# umodular_fader8.net
KiCad netlist of a schematic drawn in EAGLE
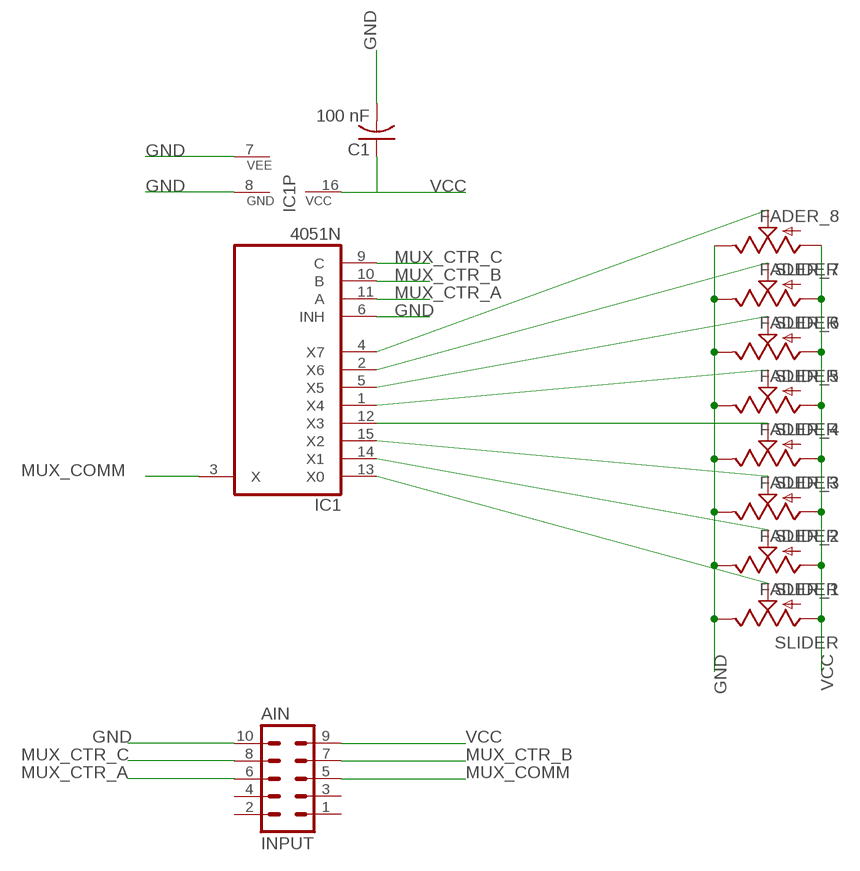
[diagram p0: schematic, sheet 1]

(export (version "E")
  (design (tool "Eeschema 10.0.6"))
  (components
    (comp (ref "AIN")
      (value "INPUT")
      (footprint "eagle-import:MA05-2")
      (libsource (lib "eagle-import") (part "MA05-2"))
    )
    (comp (ref "C1")
      (value "100 nF")
      (footprint "eagle-import:C050-024X044")
      (libsource (lib "eagle-import") (part "C-US050-024X044"))
    )
    (comp (ref "FADER_1")
      (value "SLIDER")
      (footprint "eagle-import:SLIDER")
      (libsource (lib "eagle-import") (part "SLIDER"))
    )
    (comp (ref "FADER_2")
      (value "SLIDER")
      (footprint "eagle-import:SLIDER")
      (libsource (lib "eagle-import") (part "SLIDER"))
    )
    (comp (ref "FADER_3")
      (value "SLIDER")
      (footprint "eagle-import:SLIDER")
      (libsource (lib "eagle-import") (part "SLIDER"))
    )
    (comp (ref "FADER_4")
      (value "SLIDER")
      (footprint "eagle-import:SLIDER")
      (libsource (lib "eagle-import") (part "SLIDER"))
    )
    (comp (ref "FADER_5")
      (value "SLIDER")
      (footprint "eagle-import:SLIDER")
      (libsource (lib "eagle-import") (part "SLIDER"))
    )
    (comp (ref "FADER_6")
      (value "SLIDER")
      (footprint "eagle-import:SLIDER")
      (libsource (lib "eagle-import") (part "SLIDER"))
    )
    (comp (ref "FADER_7")
      (value "SLIDER")
      (footprint "eagle-import:SLIDER")
      (libsource (lib "eagle-import") (part "SLIDER"))
    )
    (comp (ref "FADER_8")
      (value "SLIDER")
      (footprint "eagle-import:SLIDER")
      (libsource (lib "eagle-import") (part "SLIDER"))
    )
    (comp (ref "IC1")
      (value "4051N")
      (footprint "eagle-import:DIL16")
      (libsource (lib "eagle-import") (part "4051N"))
    )
  )
  (nets
    (net (code "1") (name "/GND") (class "Default")
      (node (ref "AIN") (pin "10") (pinfunction "10_10") (pintype "passive"))
      (node (ref "C1") (pin "2") (pinfunction "2_2") (pintype "passive"))
      (node (ref "FADER_1") (pin "1") (pinfunction "E_1") (pintype "passive"))
      (node (ref "FADER_2") (pin "1") (pinfunction "E_1") (pintype "passive"))
      (node (ref "FADER_3") (pin "1") (pinfunction "E_1") (pintype "passive"))
      (node (ref "FADER_4") (pin "1") (pinfunction "E_1") (pintype "passive"))
      (node (ref "FADER_5") (pin "1") (pinfunction "E_1") (pintype "passive"))
      (node (ref "FADER_6") (pin "1") (pinfunction "E_1") (pintype "passive"))
      (node (ref "FADER_7") (pin "1") (pinfunction "E_1") (pintype "passive"))
      (node (ref "FADER_8") (pin "1") (pinfunction "E_1") (pintype "passive"))
      (node (ref "IC1") (pin "6") (pinfunction "INH_6") (pintype "input"))
      (node (ref "IC1") (pin "7") (pinfunction "VEE_7") (pintype "power_in"))
      (node (ref "IC1") (pin "8") (pinfunction "GND_8") (pintype "power_in"))
    )
    (net (code "2") (name "/MUX_COMM") (class "Default")
      (node (ref "AIN") (pin "5") (pinfunction "5_5") (pintype "passive"))
      (node (ref "IC1") (pin "3") (pinfunction "X_3") (pintype "bidirectional"))
    )
    (net (code "3") (name "/MUX_CTR_A") (class "Default")
      (node (ref "AIN") (pin "6") (pinfunction "6_6") (pintype "passive"))
      (node (ref "IC1") (pin "11") (pinfunction "A_11") (pintype "input"))
    )
    (net (code "4") (name "/MUX_CTR_B") (class "Default")
      (node (ref "AIN") (pin "7") (pinfunction "7_7") (pintype "passive"))
      (node (ref "IC1") (pin "10") (pinfunction "B_10") (pintype "input"))
    )
    (net (code "5") (name "/MUX_CTR_C") (class "Default")
      (node (ref "AIN") (pin "8") (pinfunction "8_8") (pintype "passive"))
      (node (ref "IC1") (pin "9") (pinfunction "C_9") (pintype "input"))
    )
    (net (code "6") (name "/VCC") (class "Default")
      (node (ref "AIN") (pin "9") (pinfunction "9_9") (pintype "passive"))
      (node (ref "C1") (pin "1") (pinfunction "1_1") (pintype "passive"))
      (node (ref "FADER_1") (pin "3") (pinfunction "A_3") (pintype "passive"))
      (node (ref "FADER_2") (pin "3") (pinfunction "A_3") (pintype "passive"))
      (node (ref "FADER_3") (pin "3") (pinfunction "A_3") (pintype "passive"))
      (node (ref "FADER_4") (pin "3") (pinfunction "A_3") (pintype "passive"))
      (node (ref "FADER_5") (pin "3") (pinfunction "A_3") (pintype "passive"))
      (node (ref "FADER_6") (pin "3") (pinfunction "A_3") (pintype "passive"))
      (node (ref "FADER_7") (pin "3") (pinfunction "A_3") (pintype "passive"))
      (node (ref "FADER_8") (pin "3") (pinfunction "A_3") (pintype "passive"))
      (node (ref "IC1") (pin "16") (pinfunction "VCC_16") (pintype "power_in"))
    )
    (net (code "7") (name "Net-(FADER_1-S)") (class "Default")
      (node (ref "FADER_1") (pin "2A") (pinfunction "S_2A") (pintype "passive"))
      (node (ref "IC1") (pin "13") (pinfunction "X0_13") (pintype "bidirectional"))
    )
    (net (code "8") (name "Net-(FADER_2-S)") (class "Default")
      (node (ref "FADER_2") (pin "2A") (pinfunction "S_2A") (pintype "passive"))
      (node (ref "IC1") (pin "14") (pinfunction "X1_14") (pintype "bidirectional"))
    )
    (net (code "9") (name "Net-(FADER_3-S)") (class "Default")
      (node (ref "FADER_3") (pin "2A") (pinfunction "S_2A") (pintype "passive"))
      (node (ref "IC1") (pin "15") (pinfunction "X2_15") (pintype "bidirectional"))
    )
    (net (code "10") (name "Net-(FADER_4-S)") (class "Default")
      (node (ref "FADER_4") (pin "2A") (pinfunction "S_2A") (pintype "passive"))
      (node (ref "IC1") (pin "12") (pinfunction "X3_12") (pintype "bidirectional"))
    )
    (net (code "11") (name "Net-(FADER_5-S)") (class "Default")
      (node (ref "FADER_5") (pin "2A") (pinfunction "S_2A") (pintype "passive"))
      (node (ref "IC1") (pin "1") (pinfunction "X4_1") (pintype "bidirectional"))
    )
    (net (code "12") (name "Net-(FADER_6-S)") (class "Default")
      (node (ref "FADER_6") (pin "2A") (pinfunction "S_2A") (pintype "passive"))
      (node (ref "IC1") (pin "5") (pinfunction "X5_5") (pintype "bidirectional"))
    )
    (net (code "13") (name "Net-(FADER_7-S)") (class "Default")
      (node (ref "FADER_7") (pin "2A") (pinfunction "S_2A") (pintype "passive"))
      (node (ref "IC1") (pin "2") (pinfunction "X6_2") (pintype "bidirectional"))
    )
    (net (code "14") (name "Net-(FADER_8-S)") (class "Default")
      (node (ref "FADER_8") (pin "2A") (pinfunction "S_2A") (pintype "passive"))
      (node (ref "IC1") (pin "4") (pinfunction "X7_4") (pintype "bidirectional"))
    )
    (net (code "15") (name "unconnected-(AIN-Pad1)") (class "Default")
      (node (ref "AIN") (pin "1") (pinfunction "1_1") (pintype "passive"))
    )
    (net (code "16") (name "unconnected-(AIN-Pad2)") (class "Default")
      (node (ref "AIN") (pin "2") (pinfunction "2_2") (pintype "passive"))
    )
    (net (code "17") (name "unconnected-(AIN-Pad3)") (class "Default")
      (node (ref "AIN") (pin "3") (pinfunction "3_3") (pintype "passive"))
    )
    (net (code "18") (name "unconnected-(AIN-Pad4)") (class "Default")
      (node (ref "AIN") (pin "4") (pinfunction "4_4") (pintype "passive"))
    )
  )
)
